# Shield.net
KiCad netlist of a schematic drawn in EAGLE
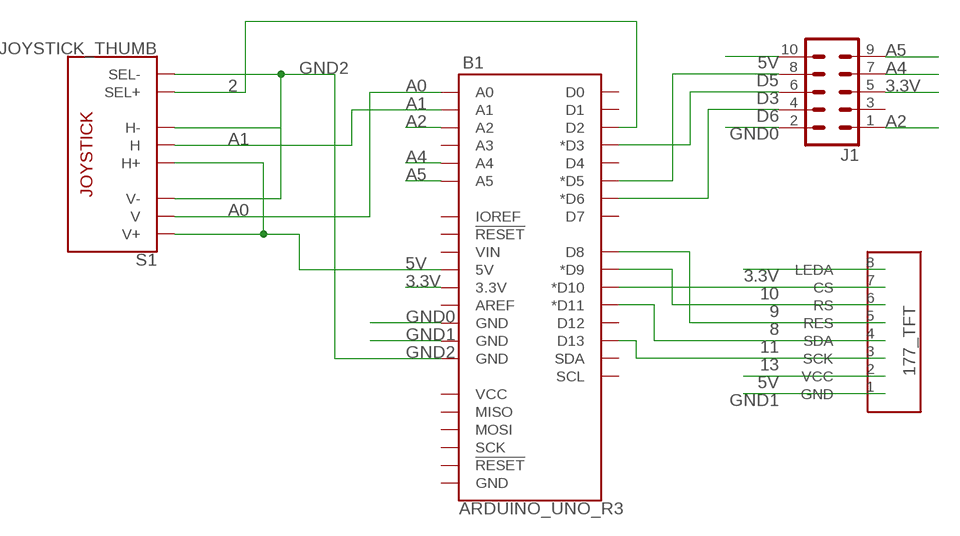
[diagram p0: schematic, sheet 1]

(export (version "E")
  (design (tool "Eeschema 10.0.6"))
  (components
    (comp (ref "1.77_TFT")
      (value "TFT_DISPL_1.77\"")
      (footprint "eagle-import:TFT_DISP")
      (libsource (lib "eagle-import") (part "TFT_DISPL_1.77{dblquote}"))
    )
    (comp (ref "B1")
      (value "ARDUINO_UNO_R3")
      (footprint "eagle-import:ARDUINO_R3")
      (libsource (lib "eagle-import") (part "ARDUINO_UNO_R3"))
    )
    (comp (ref "J1")
      (value "CONN_05X2SHD")
      (footprint "eagle-import:2X5-SHROUDED")
      (libsource (lib "eagle-import") (part "CONN_05X2SHD"))
    )
    (comp (ref "S1")
      (value "JOYSTICK_THUMB")
      (footprint "eagle-import:JOYSTICK")
      (libsource (lib "eagle-import") (part "JOYSTICK_THUMB"))
    )
  )
  (nets
    (net (code "1") (name "/2") (class "Default")
      (node (ref "B1") (pin "D2") (pinfunction "D2_D2") (pintype "bidirectional"))
      (node (ref "S1") (pin "B1A") (pinfunction "SEL+_B1A") (pintype "bidirectional"))
    )
    (net (code "2") (name "/3.3V") (class "Default")
      (node (ref "1.77_TFT") (pin "8") (pinfunction "LEDA_8") (pintype "bidirectional"))
      (node (ref "B1") (pin "3.3V") (pinfunction "3.3V_3.3V") (pintype "bidirectional"))
      (node (ref "J1") (pin "5") (pinfunction "5_5") (pintype "passive"))
    )
    (net (code "3") (name "/5V") (class "Default")
      (node (ref "1.77_TFT") (pin "2") (pinfunction "VCC_2") (pintype "bidirectional"))
      (node (ref "B1") (pin "5V") (pinfunction "5V_5V") (pintype "bidirectional"))
      (node (ref "J1") (pin "10") (pinfunction "10_10") (pintype "passive"))
      (node (ref "S1") (pin "H1") (pinfunction "H+_H1") (pintype "bidirectional"))
      (node (ref "S1") (pin "V1") (pinfunction "V+_V1") (pintype "bidirectional"))
    )
    (net (code "4") (name "/8") (class "Default")
      (node (ref "1.77_TFT") (pin "5") (pinfunction "RES_5") (pintype "bidirectional"))
      (node (ref "B1") (pin "D8") (pinfunction "D8_D8") (pintype "bidirectional"))
    )
    (net (code "5") (name "/9") (class "Default")
      (node (ref "1.77_TFT") (pin "6") (pinfunction "RS_6") (pintype "bidirectional"))
      (node (ref "B1") (pin "D9") (pinfunction "*D9_D9") (pintype "bidirectional"))
    )
    (net (code "6") (name "/10") (class "Default")
      (node (ref "1.77_TFT") (pin "7") (pinfunction "CS_7") (pintype "bidirectional"))
      (node (ref "B1") (pin "D10") (pinfunction "*D10_D10") (pintype "bidirectional"))
    )
    (net (code "7") (name "/11") (class "Default")
      (node (ref "1.77_TFT") (pin "4") (pinfunction "SDA_4") (pintype "bidirectional"))
      (node (ref "B1") (pin "D11") (pinfunction "*D11_D11") (pintype "bidirectional"))
    )
    (net (code "8") (name "/13") (class "Default")
      (node (ref "1.77_TFT") (pin "3") (pinfunction "SCK_3") (pintype "bidirectional"))
      (node (ref "B1") (pin "D13") (pinfunction "D13_D13") (pintype "bidirectional"))
    )
    (net (code "9") (name "/A0") (class "Default")
      (node (ref "B1") (pin "A0") (pinfunction "A0_A0") (pintype "bidirectional"))
      (node (ref "S1") (pin "V2") (pinfunction "V_V2") (pintype "bidirectional"))
    )
    (net (code "10") (name "/A1") (class "Default")
      (node (ref "B1") (pin "A1") (pinfunction "A1_A1") (pintype "bidirectional"))
      (node (ref "S1") (pin "H2") (pinfunction "H_H2") (pintype "bidirectional"))
    )
    (net (code "11") (name "/A2") (class "Default")
      (node (ref "B1") (pin "A2") (pinfunction "A2_A2") (pintype "bidirectional"))
      (node (ref "J1") (pin "1") (pinfunction "1_1") (pintype "passive"))
    )
    (net (code "12") (name "/A4") (class "Default")
      (node (ref "B1") (pin "A4") (pinfunction "A4_A4") (pintype "bidirectional"))
      (node (ref "J1") (pin "7") (pinfunction "7_7") (pintype "passive"))
    )
    (net (code "13") (name "/A5") (class "Default")
      (node (ref "B1") (pin "A5") (pinfunction "A5_A5") (pintype "bidirectional"))
      (node (ref "J1") (pin "9") (pinfunction "9_9") (pintype "passive"))
    )
    (net (code "14") (name "/D3") (class "Default")
      (node (ref "B1") (pin "D3") (pinfunction "*D3_D3") (pintype "bidirectional"))
      (node (ref "J1") (pin "6") (pinfunction "6_6") (pintype "passive"))
    )
    (net (code "15") (name "/D5") (class "Default")
      (node (ref "B1") (pin "D5") (pinfunction "*D5_D5") (pintype "bidirectional"))
      (node (ref "J1") (pin "8") (pinfunction "8_8") (pintype "passive"))
    )
    (net (code "16") (name "/D6") (class "Default")
      (node (ref "B1") (pin "D6") (pinfunction "*D6_D6") (pintype "bidirectional"))
      (node (ref "J1") (pin "4") (pinfunction "4_4") (pintype "passive"))
    )
    (net (code "17") (name "/GND0") (class "Default")
      (node (ref "B1") (pin "GND@4") (pinfunction "GND_GND@4") (pintype "bidirectional"))
      (node (ref "J1") (pin "2") (pinfunction "2_2") (pintype "passive"))
    )
    (net (code "18") (name "/GND1") (class "Default")
      (node (ref "1.77_TFT") (pin "1") (pinfunction "GND_1") (pintype "bidirectional"))
      (node (ref "B1") (pin "GND@3") (pinfunction "GND_GND@3") (pintype "bidirectional"))
    )
    (net (code "19") (name "/GND2") (class "Default")
      (node (ref "B1") (pin "GND@2") (pinfunction "GND_GND@2") (pintype "bidirectional"))
      (node (ref "S1") (pin "B2A") (pinfunction "SEL-_B2A") (pintype "bidirectional"))
      (node (ref "S1") (pin "H3") (pinfunction "H-_H3") (pintype "bidirectional"))
      (node (ref "S1") (pin "V3") (pinfunction "V-_V3") (pintype "bidirectional"))
    )
    (net (code "20") (name "unconnected-(B1-GND-PadGND@1)") (class "Default")
      (node (ref "B1") (pin "GND@1") (pinfunction "GND_GND@1") (pintype "bidirectional"))
    )
    (net (code "21") (name "unconnected-(B1-PadA3)") (class "Default")
      (node (ref "B1") (pin "A3") (pinfunction "A3_A3") (pintype "bidirectional"))
    )
    (net (code "22") (name "unconnected-(B1-PadAREF)") (class "Default")
      (node (ref "B1") (pin "AREF") (pinfunction "AREF_AREF") (pintype "bidirectional"))
    )
    (net (code "23") (name "unconnected-(B1-PadD0)") (class "Default")
      (node (ref "B1") (pin "D0") (pinfunction "D0_D0") (pintype "bidirectional"))
    )
    (net (code "24") (name "unconnected-(B1-PadD1)") (class "Default")
      (node (ref "B1") (pin "D1") (pinfunction "D1_D1") (pintype "bidirectional"))
    )
    (net (code "25") (name "unconnected-(B1-PadD4)") (class "Default")
      (node (ref "B1") (pin "D4") (pinfunction "D4_D4") (pintype "bidirectional"))
    )
    (net (code "26") (name "unconnected-(B1-PadD7)") (class "Default")
      (node (ref "B1") (pin "D7") (pinfunction "D7_D7") (pintype "bidirectional"))
    )
    (net (code "27") (name "unconnected-(B1-PadD12)") (class "Default")
      (node (ref "B1") (pin "D12") (pinfunction "D12_D12") (pintype "bidirectional"))
    )
    (net (code "28") (name "unconnected-(B1-PadIOREF)") (class "Default")
      (node (ref "B1") (pin "IOREF") (pinfunction "IOREF_IOREF") (pintype "bidirectional"))
    )
    (net (code "29") (name "unconnected-(B1-PadMISO)") (class "Default")
      (node (ref "B1") (pin "MISO") (pinfunction "MISO_MISO") (pintype "bidirectional"))
    )
    (net (code "30") (name "unconnected-(B1-PadMOSI)") (class "Default")
      (node (ref "B1") (pin "MOSI") (pinfunction "MOSI_MOSI") (pintype "bidirectional"))
    )
    (net (code "31") (name "unconnected-(B1-PadSCK)") (class "Default")
      (node (ref "B1") (pin "SCK") (pinfunction "SCK_SCK") (pintype "bidirectional"))
    )
    (net (code "32") (name "unconnected-(B1-PadSCL)") (class "Default")
      (node (ref "B1") (pin "SCL") (pinfunction "SCL_SCL") (pintype "bidirectional"))
    )
    (net (code "33") (name "unconnected-(B1-PadSDA)") (class "Default")
      (node (ref "B1") (pin "SDA") (pinfunction "SDA_SDA") (pintype "bidirectional"))
    )
    (net (code "34") (name "unconnected-(B1-PadVCC)") (class "Default")
      (node (ref "B1") (pin "VCC") (pinfunction "VCC_VCC") (pintype "bidirectional"))
    )
    (net (code "35") (name "unconnected-(B1-PadVIN)") (class "Default")
      (node (ref "B1") (pin "VIN") (pinfunction "VIN_VIN") (pintype "bidirectional"))
    )
    (net (code "36") (name "unconnected-(B1-~{RESET}-PadRESET@1)") (class "Default")
      (node (ref "B1") (pin "RESET@1") (pinfunction "~{RESET}_RESET@1") (pintype "bidirectional"))
    )
    (net (code "37") (name "unconnected-(B1-~{RESET}-PadRESET@2)") (class "Default")
      (node (ref "B1") (pin "RESET@2") (pinfunction "~{RESET}_RESET@2") (pintype "bidirectional"))
    )
    (net (code "38") (name "unconnected-(J1-Pad3)") (class "Default")
      (node (ref "J1") (pin "3") (pinfunction "3_3") (pintype "passive"))
    )
  )
)
